# gameboyzero-double.net
KiCad netlist of a schematic drawn in EAGLE
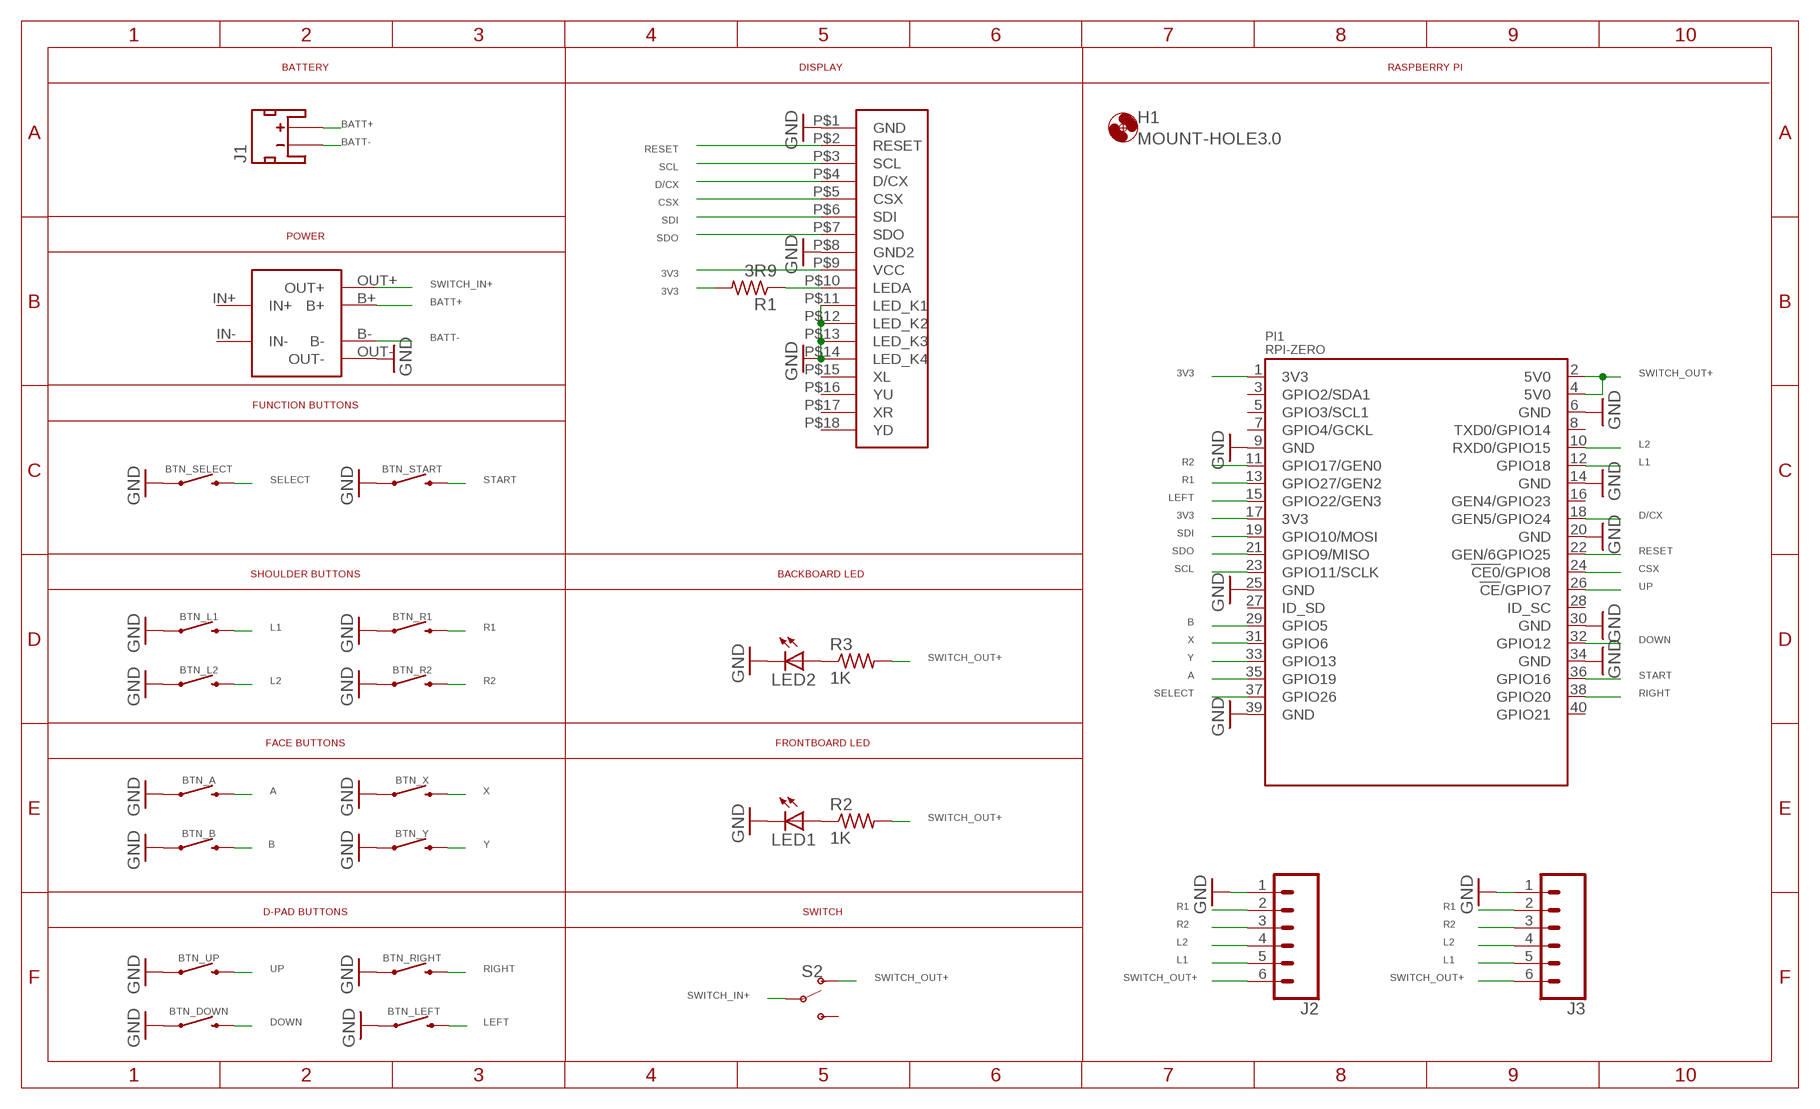
[diagram p0: schematic, sheet 1]

(export (version "E")
  (design (tool "Eeschema 10.0.6"))
  (components
    (comp (ref "BTN_A")
      (value "MOMENTARY-SWITCH-SPST-SMD-12MM")
      (footprint "eagle-import:TACTILE_SWITCH_SMD_12MM")
      (libsource (lib "eagle-import") (part "MOMENTARY-SWITCH-SPST-SMD-12MM"))
    )
    (comp (ref "BTN_B")
      (value "MOMENTARY-SWITCH-SPST-SMD-12MM")
      (footprint "eagle-import:TACTILE_SWITCH_SMD_12MM")
      (libsource (lib "eagle-import") (part "MOMENTARY-SWITCH-SPST-SMD-12MM"))
    )
    (comp (ref "BTN_DOWN")
      (value "MOMENTARY-SWITCH-SPST-SMD-6.2MM-TALL")
      (footprint "eagle-import:TACTILE_SWITCH_SMD_6.2MM_TALL")
      (libsource (lib "eagle-import") (part "MOMENTARY-SWITCH-SPST-SMD-6.2MM-TALL"))
    )
    (comp (ref "BTN_L1")
      (value "MOMENTARY-SWITCH-SPST-SMD-12MM")
      (footprint "eagle-import:TACTILE_SWITCH_SMD_12MM")
      (libsource (lib "eagle-import") (part "MOMENTARY-SWITCH-SPST-SMD-12MM"))
    )
    (comp (ref "BTN_L2")
      (value "MOMENTARY-SWITCH-SPST-SMD-12MM")
      (footprint "eagle-import:TACTILE_SWITCH_SMD_12MM")
      (libsource (lib "eagle-import") (part "MOMENTARY-SWITCH-SPST-SMD-12MM"))
    )
    (comp (ref "BTN_LEFT")
      (value "MOMENTARY-SWITCH-SPST-SMD-6.2MM-TALL")
      (footprint "eagle-import:TACTILE_SWITCH_SMD_6.2MM_TALL")
      (libsource (lib "eagle-import") (part "MOMENTARY-SWITCH-SPST-SMD-6.2MM-TALL"))
    )
    (comp (ref "BTN_R1")
      (value "MOMENTARY-SWITCH-SPST-SMD-12MM")
      (footprint "eagle-import:TACTILE_SWITCH_SMD_12MM")
      (libsource (lib "eagle-import") (part "MOMENTARY-SWITCH-SPST-SMD-12MM"))
    )
    (comp (ref "BTN_R2")
      (value "MOMENTARY-SWITCH-SPST-SMD-12MM")
      (footprint "eagle-import:TACTILE_SWITCH_SMD_12MM")
      (libsource (lib "eagle-import") (part "MOMENTARY-SWITCH-SPST-SMD-12MM"))
    )
    (comp (ref "BTN_RIGHT")
      (value "MOMENTARY-SWITCH-SPST-SMD-6.2MM-TALL")
      (footprint "eagle-import:TACTILE_SWITCH_SMD_6.2MM_TALL")
      (libsource (lib "eagle-import") (part "MOMENTARY-SWITCH-SPST-SMD-6.2MM-TALL"))
    )
    (comp (ref "BTN_SELECT")
      (value "MOMENTARY-SWITCH-SPST-SMD-6.0X3.5MM")
      (footprint "eagle-import:TACTILE_SWITCH_SMD_6.0X3.5MM")
      (libsource (lib "eagle-import") (part "MOMENTARY-SWITCH-SPST-SMD-6.0X3.5MM"))
    )
    (comp (ref "BTN_START")
      (value "MOMENTARY-SWITCH-SPST-SMD-6.0X3.5MM")
      (footprint "eagle-import:TACTILE_SWITCH_SMD_6.0X3.5MM")
      (libsource (lib "eagle-import") (part "MOMENTARY-SWITCH-SPST-SMD-6.0X3.5MM"))
    )
    (comp (ref "BTN_UP")
      (value "MOMENTARY-SWITCH-SPST-SMD-6.2MM-TALL")
      (footprint "eagle-import:TACTILE_SWITCH_SMD_6.2MM_TALL")
      (libsource (lib "eagle-import") (part "MOMENTARY-SWITCH-SPST-SMD-6.2MM-TALL"))
    )
    (comp (ref "BTN_X")
      (value "MOMENTARY-SWITCH-SPST-SMD-12MM")
      (footprint "eagle-import:TACTILE_SWITCH_SMD_12MM")
      (libsource (lib "eagle-import") (part "MOMENTARY-SWITCH-SPST-SMD-12MM"))
    )
    (comp (ref "BTN_Y")
      (value "MOMENTARY-SWITCH-SPST-SMD-12MM")
      (footprint "eagle-import:TACTILE_SWITCH_SMD_12MM")
      (libsource (lib "eagle-import") (part "MOMENTARY-SWITCH-SPST-SMD-12MM"))
    )
    (comp (ref "H1")
      (value "MOUNT-HOLE3.0")
      (footprint "eagle-import:3,0")
      (libsource (lib "eagle-import") (part "MOUNT-HOLE3.0"))
    )
    (comp (ref "J1")
      (value "JST_2MM_MALE")
      (footprint "eagle-import:JST-2-SMD")
      (libsource (lib "eagle-import") (part "JST_2MM_MALE"))
    )
    (comp (ref "J2")
      (value "CONN_06SILK_FEMALE_PTH")
      (footprint "eagle-import:1X06")
      (libsource (lib "eagle-import") (part "CONN_06SILK_FEMALE_PTH"))
    )
    (comp (ref "J3")
      (value "CONN_06SILK_FEMALE_PTH")
      (footprint "eagle-import:1X06")
      (libsource (lib "eagle-import") (part "CONN_06SILK_FEMALE_PTH"))
    )
    (comp (ref "LED1")
      (value "LEDCHIPLED_0805")
      (footprint "eagle-import:CHIPLED_0805")
      (libsource (lib "eagle-import") (part "LEDCHIPLED_0805"))
    )
    (comp (ref "LED2")
      (value "LEDCHIPLED_0805")
      (footprint "eagle-import:CHIPLED_0805")
      (libsource (lib "eagle-import") (part "LEDCHIPLED_0805"))
    )
    (comp (ref "PI1")
      (value "RPI-ZERO")
      (footprint "eagle-import:RASPBERRYPI_BASTELSTUBE_V13_RASPI_BOARD_B+_FULL")
      (libsource (lib "eagle-import") (part "RPI-ZERO"))
    )
    (comp (ref "POWER1")
      (value "03962A")
      (footprint "eagle-import:03962A")
      (libsource (lib "eagle-import") (part "03962A"))
    )
    (comp (ref "R1")
      (value "3R9")
      (footprint "eagle-import:R0805")
      (libsource (lib "eagle-import") (part "R-US_R0805"))
    )
    (comp (ref "R2")
      (value "1K")
      (footprint "eagle-import:R0805")
      (libsource (lib "eagle-import") (part "R-US_R0805"))
    )
    (comp (ref "R3")
      (value "1K")
      (footprint "eagle-import:R0805")
      (libsource (lib "eagle-import") (part "R-US_R0805"))
    )
    (comp (ref "S2")
      (value "SWITCH-SPDT-SMD-RIGHT-ANGLE")
      (footprint "eagle-import:SWITCH_SPST_SMD_A")
      (libsource (lib "eagle-import") (part "SWITCH-SPDT-SMD-RIGHT-ANGLE"))
    )
    (comp (ref "SCREEN1")
      (value "GAMEBOYZEROHANDHELDDISPLAYS-2.8")
      (footprint "eagle-import:GAMEBOYZEROHANDHELDDISPLAYS-2.8")
      (libsource (lib "eagle-import") (part "GAMEBOYZEROHANDHELDDISPLAYS-2.8"))
    )
  )
  (nets
    (net (code "1") (name "/3V3") (class "Default")
      (node (ref "PI1") (pin "1") (pinfunction "3V3_1") (pintype "power_in"))
      (node (ref "PI1") (pin "17") (pinfunction "3V3_17") (pintype "power_in"))
      (node (ref "R1") (pin "2") (pinfunction "2_2") (pintype "passive"))
      (node (ref "SCREEN1") (pin "P$9") (pinfunction "VCC_P$9") (pintype "bidirectional"))
    )
    (net (code "2") (name "/A") (class "Default")
      (node (ref "BTN_A") (pin "3") (pinfunction "2_3") (pintype "passive"))
      (node (ref "PI1") (pin "35") (pinfunction "GPIO19_35") (pintype "bidirectional"))
    )
    (net (code "3") (name "/B") (class "Default")
      (node (ref "BTN_B") (pin "3") (pinfunction "2_3") (pintype "passive"))
      (node (ref "PI1") (pin "29") (pinfunction "GPIO5_29") (pintype "bidirectional"))
    )
    (net (code "4") (name "/BATT+") (class "Default")
      (node (ref "J1") (pin "2") (pinfunction "+_2") (pintype "bidirectional"))
      (node (ref "POWER1") (pin "B+") (pinfunction "B+_B+") (pintype "bidirectional"))
    )
    (net (code "5") (name "/BATT-") (class "Default")
      (node (ref "J1") (pin "1") (pinfunction "-_1") (pintype "bidirectional"))
      (node (ref "POWER1") (pin "B-") (pinfunction "B-_B-") (pintype "bidirectional"))
    )
    (net (code "6") (name "/CSX") (class "Default")
      (node (ref "PI1") (pin "24") (pinfunction "~{CE0}/GPIO8_24") (pintype "bidirectional"))
      (node (ref "SCREEN1") (pin "P$5") (pinfunction "CSX_P$5") (pintype "bidirectional"))
    )
    (net (code "7") (name "/DOWN") (class "Default")
      (node (ref "BTN_DOWN") (pin "B2") (pinfunction "2_B2") (pintype "passive"))
      (node (ref "PI1") (pin "32") (pinfunction "GPIO12_32") (pintype "bidirectional"))
    )
    (net (code "8") (name "/D{slash}CX") (class "Default")
      (node (ref "PI1") (pin "18") (pinfunction "GEN5/GPIO24_18") (pintype "bidirectional"))
      (node (ref "SCREEN1") (pin "P$4") (pinfunction "D/CX_P$4") (pintype "bidirectional"))
    )
    (net (code "9") (name "/L1") (class "Default")
      (node (ref "BTN_L1") (pin "3") (pinfunction "2_3") (pintype "passive"))
      (node (ref "J2") (pin "5") (pinfunction "5_5") (pintype "passive"))
      (node (ref "J3") (pin "5") (pinfunction "5_5") (pintype "passive"))
      (node (ref "PI1") (pin "12") (pinfunction "GPIO18_12") (pintype "bidirectional"))
    )
    (net (code "10") (name "/L2") (class "Default")
      (node (ref "BTN_L2") (pin "3") (pinfunction "2_3") (pintype "passive"))
      (node (ref "J2") (pin "4") (pinfunction "4_4") (pintype "passive"))
      (node (ref "J3") (pin "4") (pinfunction "4_4") (pintype "passive"))
      (node (ref "PI1") (pin "10") (pinfunction "RXD0/GPIO15_10") (pintype "bidirectional"))
    )
    (net (code "11") (name "/LEFT") (class "Default")
      (node (ref "BTN_LEFT") (pin "B2") (pinfunction "2_B2") (pintype "passive"))
      (node (ref "PI1") (pin "15") (pinfunction "GPIO22/GEN3_15") (pintype "bidirectional"))
    )
    (net (code "12") (name "/R1") (class "Default")
      (node (ref "BTN_R1") (pin "3") (pinfunction "2_3") (pintype "passive"))
      (node (ref "J2") (pin "2") (pinfunction "2_2") (pintype "passive"))
      (node (ref "J3") (pin "2") (pinfunction "2_2") (pintype "passive"))
      (node (ref "PI1") (pin "13") (pinfunction "GPIO27/GEN2_13") (pintype "bidirectional"))
    )
    (net (code "13") (name "/R2") (class "Default")
      (node (ref "BTN_R2") (pin "3") (pinfunction "2_3") (pintype "passive"))
      (node (ref "J2") (pin "3") (pinfunction "3_3") (pintype "passive"))
      (node (ref "J3") (pin "3") (pinfunction "3_3") (pintype "passive"))
      (node (ref "PI1") (pin "11") (pinfunction "GPIO17/GEN0_11") (pintype "bidirectional"))
    )
    (net (code "14") (name "/RESET") (class "Default")
      (node (ref "PI1") (pin "22") (pinfunction "GEN/6GPIO25_22") (pintype "bidirectional"))
      (node (ref "SCREEN1") (pin "P$2") (pinfunction "RESET_P$2") (pintype "bidirectional"))
    )
    (net (code "15") (name "/RIGHT") (class "Default")
      (node (ref "BTN_RIGHT") (pin "B2") (pinfunction "2_B2") (pintype "passive"))
      (node (ref "PI1") (pin "38") (pinfunction "GPIO20_38") (pintype "bidirectional"))
    )
    (net (code "16") (name "/SCL") (class "Default")
      (node (ref "PI1") (pin "23") (pinfunction "GPIO11/SCLK_23") (pintype "bidirectional"))
      (node (ref "SCREEN1") (pin "P$3") (pinfunction "SCL_P$3") (pintype "bidirectional"))
    )
    (net (code "17") (name "/SDI") (class "Default")
      (node (ref "PI1") (pin "19") (pinfunction "GPIO10/MOSI_19") (pintype "bidirectional"))
      (node (ref "SCREEN1") (pin "P$6") (pinfunction "SDI_P$6") (pintype "bidirectional"))
    )
    (net (code "18") (name "/SDO") (class "Default")
      (node (ref "PI1") (pin "21") (pinfunction "GPIO9/MISO_21") (pintype "bidirectional"))
      (node (ref "SCREEN1") (pin "P$7") (pinfunction "SDO_P$7") (pintype "bidirectional"))
    )
    (net (code "19") (name "/SELECT") (class "Default")
      (node (ref "BTN_SELECT") (pin "2") (pinfunction "2_2") (pintype "passive"))
      (node (ref "PI1") (pin "37") (pinfunction "GPIO26_37") (pintype "bidirectional"))
    )
    (net (code "20") (name "/START") (class "Default")
      (node (ref "BTN_START") (pin "2") (pinfunction "2_2") (pintype "passive"))
      (node (ref "PI1") (pin "36") (pinfunction "GPIO16_36") (pintype "bidirectional"))
    )
    (net (code "21") (name "/SWITCH_IN+") (class "Default")
      (node (ref "POWER1") (pin "OUT+") (pinfunction "OUT+_OUT+") (pintype "bidirectional"))
      (node (ref "S2") (pin "2") (pinfunction "P_2") (pintype "passive"))
    )
    (net (code "22") (name "/SWITCH_OUT+") (class "Default")
      (node (ref "J2") (pin "6") (pinfunction "6_6") (pintype "passive"))
      (node (ref "J3") (pin "6") (pinfunction "6_6") (pintype "passive"))
      (node (ref "PI1") (pin "2") (pinfunction "5V0_2") (pintype "power_in"))
      (node (ref "PI1") (pin "4") (pinfunction "5V0_4") (pintype "power_in"))
      (node (ref "R2") (pin "2") (pinfunction "2_2") (pintype "passive"))
      (node (ref "R3") (pin "2") (pinfunction "2_2") (pintype "passive"))
      (node (ref "S2") (pin "1") (pinfunction "O_1") (pintype "passive"))
    )
    (net (code "23") (name "/UP") (class "Default")
      (node (ref "BTN_UP") (pin "B2") (pinfunction "2_B2") (pintype "passive"))
      (node (ref "PI1") (pin "26") (pinfunction "~{CE}/GPIO7_26") (pintype "bidirectional"))
    )
    (net (code "24") (name "/X") (class "Default")
      (node (ref "BTN_X") (pin "3") (pinfunction "2_3") (pintype "passive"))
      (node (ref "PI1") (pin "31") (pinfunction "GPIO6_31") (pintype "bidirectional"))
    )
    (net (code "25") (name "/Y") (class "Default")
      (node (ref "BTN_Y") (pin "3") (pinfunction "2_3") (pintype "passive"))
      (node (ref "PI1") (pin "33") (pinfunction "GPIO13_33") (pintype "bidirectional"))
    )
    (net (code "26") (name "GND") (class "Default")
      (node (ref "BTN_A") (pin "1") (pinfunction "1_1") (pintype "passive"))
      (node (ref "BTN_B") (pin "1") (pinfunction "1_1") (pintype "passive"))
      (node (ref "BTN_DOWN") (pin "A2") (pinfunction "1_A2") (pintype "passive"))
      (node (ref "BTN_L1") (pin "1") (pinfunction "1_1") (pintype "passive"))
      (node (ref "BTN_L2") (pin "1") (pinfunction "1_1") (pintype "passive"))
      (node (ref "BTN_LEFT") (pin "A2") (pinfunction "1_A2") (pintype "passive"))
      (node (ref "BTN_R1") (pin "1") (pinfunction "1_1") (pintype "passive"))
      (node (ref "BTN_R2") (pin "1") (pinfunction "1_1") (pintype "passive"))
      (node (ref "BTN_RIGHT") (pin "A2") (pinfunction "1_A2") (pintype "passive"))
      (node (ref "BTN_SELECT") (pin "1") (pinfunction "1_1") (pintype "passive"))
      (node (ref "BTN_START") (pin "1") (pinfunction "1_1") (pintype "passive"))
      (node (ref "BTN_UP") (pin "A2") (pinfunction "1_A2") (pintype "passive"))
      (node (ref "BTN_X") (pin "1") (pinfunction "1_1") (pintype "passive"))
      (node (ref "BTN_Y") (pin "1") (pinfunction "1_1") (pintype "passive"))
      (node (ref "J2") (pin "1") (pinfunction "1_1") (pintype "passive"))
      (node (ref "J3") (pin "1") (pinfunction "1_1") (pintype "passive"))
      (node (ref "LED1") (pin "C") (pinfunction "C_C") (pintype "passive"))
      (node (ref "LED2") (pin "C") (pinfunction "C_C") (pintype "passive"))
      (node (ref "PI1") (pin "14") (pinfunction "GND_14") (pintype "power_in"))
      (node (ref "PI1") (pin "20") (pinfunction "GND_20") (pintype "power_in"))
      (node (ref "PI1") (pin "25") (pinfunction "GND_25") (pintype "power_in"))
      (node (ref "PI1") (pin "30") (pinfunction "GND_30") (pintype "power_in"))
      (node (ref "PI1") (pin "34") (pinfunction "GND_34") (pintype "power_in"))
      (node (ref "PI1") (pin "39") (pinfunction "GND_39") (pintype "power_in"))
      (node (ref "PI1") (pin "6") (pinfunction "GND_6") (pintype "power_in"))
      (node (ref "PI1") (pin "9") (pinfunction "GND_9") (pintype "power_in"))
      (node (ref "POWER1") (pin "OUT-") (pinfunction "OUT-_OUT-") (pintype "bidirectional"))
      (node (ref "SCREEN1") (pin "P$1") (pinfunction "GND_P$1") (pintype "bidirectional"))
      (node (ref "SCREEN1") (pin "P$11") (pinfunction "LED_K1_P$11") (pintype "bidirectional"))
      (node (ref "SCREEN1") (pin "P$12") (pinfunction "LED_K2_P$12") (pintype "bidirectional"))
      (node (ref "SCREEN1") (pin "P$13") (pinfunction "LED_K3_P$13") (pintype "bidirectional"))
      (node (ref "SCREEN1") (pin "P$14") (pinfunction "LED_K4_P$14") (pintype "bidirectional"))
      (node (ref "SCREEN1") (pin "P$8") (pinfunction "GND2_P$8") (pintype "bidirectional"))
    )
    (net (code "27") (name "Net-(LED1-PadA)") (class "Default")
      (node (ref "LED1") (pin "A") (pinfunction "A_A") (pintype "passive"))
      (node (ref "R2") (pin "1") (pinfunction "1_1") (pintype "passive"))
    )
    (net (code "28") (name "Net-(LED2-PadA)") (class "Default")
      (node (ref "LED2") (pin "A") (pinfunction "A_A") (pintype "passive"))
      (node (ref "R3") (pin "1") (pinfunction "1_1") (pintype "passive"))
    )
    (net (code "29") (name "Net-(SCREEN1-LEDA)") (class "Default")
      (node (ref "R1") (pin "1") (pinfunction "1_1") (pintype "passive"))
      (node (ref "SCREEN1") (pin "P$10") (pinfunction "LEDA_P$10") (pintype "bidirectional"))
    )
    (net (code "30") (name "unconnected-(J1-PAD1-PadNC1)") (class "Default")
      (node (ref "J1") (pin "NC1") (pinfunction "PAD1_NC1") (pintype "bidirectional"))
    )
    (net (code "31") (name "unconnected-(J1-PAD2-PadNC2)") (class "Default")
      (node (ref "J1") (pin "NC2") (pinfunction "PAD2_NC2") (pintype "bidirectional"))
    )
    (net (code "32") (name "unconnected-(PI1-GEN4{slash}GPIO23-Pad16)") (class "Default")
      (node (ref "PI1") (pin "16") (pinfunction "GEN4/GPIO23_16") (pintype "bidirectional"))
    )
    (net (code "33") (name "unconnected-(PI1-GPIO2{slash}SDA1-Pad3)") (class "Default")
      (node (ref "PI1") (pin "3") (pinfunction "GPIO2/SDA1_3") (pintype "bidirectional"))
    )
    (net (code "34") (name "unconnected-(PI1-GPIO3{slash}SCL1-Pad5)") (class "Default")
      (node (ref "PI1") (pin "5") (pinfunction "GPIO3/SCL1_5") (pintype "bidirectional"))
    )
    (net (code "35") (name "unconnected-(PI1-GPIO4{slash}GCKL-Pad7)") (class "Default")
      (node (ref "PI1") (pin "7") (pinfunction "GPIO4/GCKL_7") (pintype "bidirectional"))
    )
    (net (code "36") (name "unconnected-(PI1-GPIO21-Pad40)") (class "Default")
      (node (ref "PI1") (pin "40") (pinfunction "GPIO21_40") (pintype "bidirectional"))
    )
    (net (code "37") (name "unconnected-(PI1-ID_SC-Pad28)") (class "Default")
      (node (ref "PI1") (pin "28") (pinfunction "ID_SC_28") (pintype "bidirectional"))
    )
    (net (code "38") (name "unconnected-(PI1-ID_SD-Pad27)") (class "Default")
      (node (ref "PI1") (pin "27") (pinfunction "ID_SD_27") (pintype "bidirectional"))
    )
    (net (code "39") (name "unconnected-(PI1-TXD0{slash}GPIO14-Pad8)") (class "Default")
      (node (ref "PI1") (pin "8") (pinfunction "TXD0/GPIO14_8") (pintype "bidirectional"))
    )
    (net (code "40") (name "unconnected-(POWER1-PadIN+)") (class "Default")
      (node (ref "POWER1") (pin "IN+") (pinfunction "IN+_IN+") (pintype "bidirectional"))
    )
    (net (code "41") (name "unconnected-(POWER1-PadIN-)") (class "Default")
      (node (ref "POWER1") (pin "IN-") (pinfunction "IN-_IN-") (pintype "bidirectional"))
    )
    (net (code "42") (name "unconnected-(S2-S-Pad3)") (class "Default")
      (node (ref "S2") (pin "3") (pinfunction "S_3") (pintype "passive"))
    )
    (net (code "43") (name "unconnected-(SCREEN1-XL-PadP$15)") (class "Default")
      (node (ref "SCREEN1") (pin "P$15") (pinfunction "XL_P$15") (pintype "bidirectional"))
    )
    (net (code "44") (name "unconnected-(SCREEN1-XR-PadP$17)") (class "Default")
      (node (ref "SCREEN1") (pin "P$17") (pinfunction "XR_P$17") (pintype "bidirectional"))
    )
    (net (code "45") (name "unconnected-(SCREEN1-YD-PadP$18)") (class "Default")
      (node (ref "SCREEN1") (pin "P$18") (pinfunction "YD_P$18") (pintype "bidirectional"))
    )
    (net (code "46") (name "unconnected-(SCREEN1-YU-PadP$16)") (class "Default")
      (node (ref "SCREEN1") (pin "P$16") (pinfunction "YU_P$16") (pintype "bidirectional"))
    )
  )
)
